# Team26vFinal.net
KiCad netlist of a schematic drawn in EAGLE
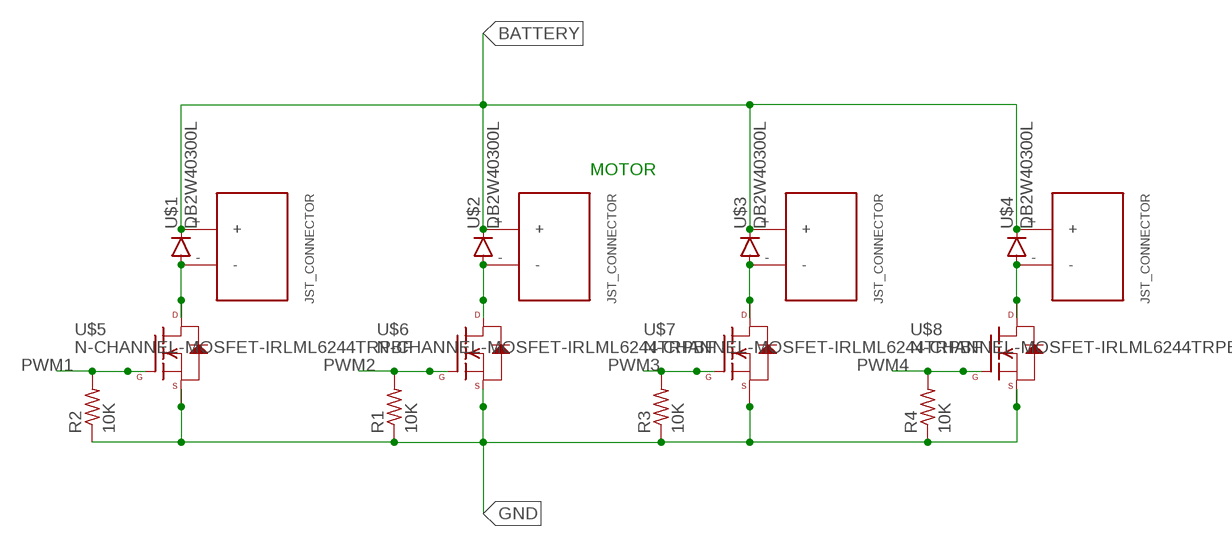
[diagram p0: schematic, sheet 1]
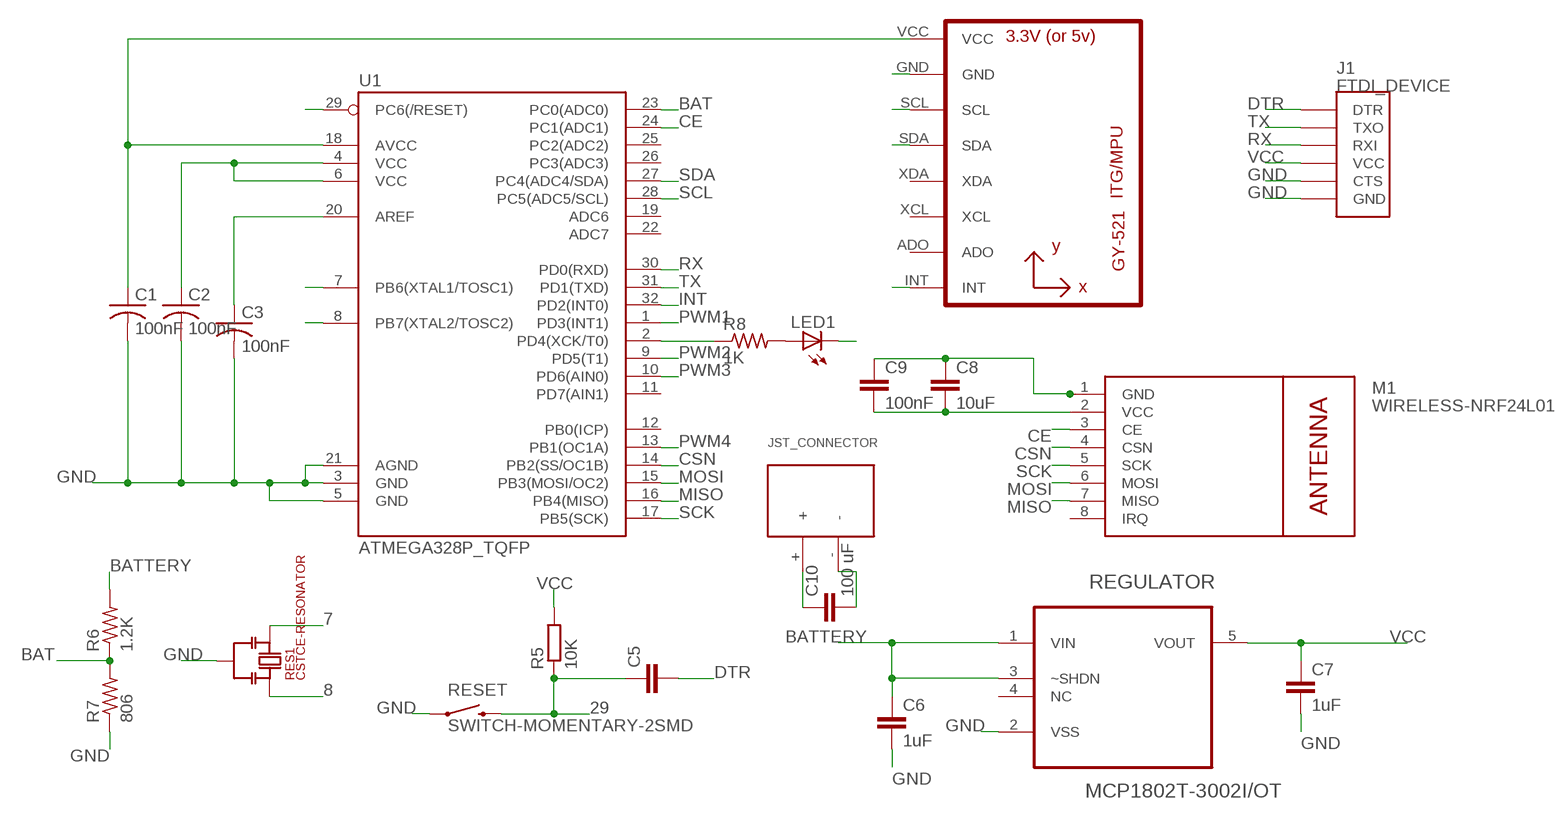
[diagram p1: schematic, sheet 2]

(export (version "E")
  (design (tool "Eeschema 10.0.6"))
  (components
    (comp (ref "C1")
      (value "100nF")
      (footprint "eagle-import:C0603")
      (libsource (lib "eagle-import") (part "C-USC0603"))
    )
    (comp (ref "C2")
      (value "100nF")
      (footprint "eagle-import:C0603")
      (libsource (lib "eagle-import") (part "C-USC0603"))
    )
    (comp (ref "C3")
      (value "100nF")
      (footprint "eagle-import:C0603")
      (libsource (lib "eagle-import") (part "C-USC0603"))
    )
    (comp (ref "C5")
      (value "C-EUC0603")
      (footprint "eagle-import:C0603")
      (libsource (lib "eagle-import") (part "C-EUC0603"))
    )
    (comp (ref "C6")
      (value "1uF")
      (footprint "eagle-import:C0603")
      (libsource (lib "eagle-import") (part "C-EUC0603"))
    )
    (comp (ref "C7")
      (value "1uF")
      (footprint "eagle-import:C0603")
      (libsource (lib "eagle-import") (part "C-EUC0603"))
    )
    (comp (ref "C8")
      (value "10uF")
      (footprint "eagle-import:C0603")
      (libsource (lib "eagle-import") (part "C-EUC0603"))
    )
    (comp (ref "C9")
      (value "100nF")
      (footprint "eagle-import:C0603")
      (libsource (lib "eagle-import") (part "C-EUC0603"))
    )
    (comp (ref "C10")
      (value "100 uF")
      (footprint "eagle-import:C1210")
      (libsource (lib "eagle-import") (part "C-EUC1210"))
    )
    (comp (ref "J1")
      (value "FTDI_DEVICE")
      (footprint "eagle-import:FTDI_DEVICE_SIDE")
      (libsource (lib "eagle-import") (part "FTDI_DEVICE"))
    )
    (comp (ref "LED1")
      (value "LEDCHIP-LED0603")
      (footprint "eagle-import:CHIP-LED0603")
      (libsource (lib "eagle-import") (part "LEDCHIP-LED0603"))
    )
    (comp (ref "M1")
      (value "WIRELESS-NRF24L01")
      (footprint "eagle-import:WIRELESS-NRF24L01")
      (libsource (lib "eagle-import") (part "WIRELESS-NRF24L01"))
    )
    (comp (ref "R5")
      (value "10K")
      (footprint "eagle-import:R0603")
      (libsource (lib "eagle-import") (part "R-EU_R0603"))
    )
    (comp (ref "R6")
      (value "1.2K")
      (footprint "eagle-import:R0603")
      (libsource (lib "eagle-import") (part "resistor_R-US_R0603"))
    )
    (comp (ref "R7")
      (value "806")
      (footprint "eagle-import:R0603")
      (libsource (lib "eagle-import") (part "resistor_R-US_R0603"))
    )
    (comp (ref "R8")
      (value "1K")
      (footprint "eagle-import:R0603")
      (libsource (lib "eagle-import") (part "resistor_R-US_R0603"))
    )
    (comp (ref "REGULATOR")
      (value "MCP1802T-3002I/OT")
      (footprint "eagle-import:SOT95P270X145-5N")
      (libsource (lib "eagle-import") (part "MCP1802T-3002I/OT"))
    )
    (comp (ref "RES1")
      (value "CSTCE-RESONATOR")
      (footprint "eagle-import:CSTCE16M0V53-R0")
      (libsource (lib "eagle-import") (part "CSTCE-RESONATOR"))
    )
    (comp (ref "RESET")
      (value "SWITCH-MOMENTARY-2SMD")
      (footprint "eagle-import:TACTILE-SWITCH-SMD")
      (libsource (lib "eagle-import") (part "SWITCH-MOMENTARY-2SMD"))
    )
    (comp (ref "U$9")
      (value "JST_CONNECTOR_FEMALE")
      (footprint "eagle-import:JST_CONNECTOR_FEMALE")
      (libsource (lib "eagle-import") (part "JST_CONNECTOR_FEMALE"))
    )
    (comp (ref "U1")
      (value "ATMEGA328P_TQFP")
      (footprint "eagle-import:TQFP32-08")
      (libsource (lib "eagle-import") (part "ATMEGA328P_TQFP"))
    )
    (comp (ref "U2")
      (value "GY-521MPU6050")
      (footprint "eagle-import:GY-521")
      (libsource (lib "eagle-import") (part "GY-521MPU6050"))
    )
    (comp (ref "MOTOR")
      (value "JST_CONNECTOR_FEMALE")
      (footprint "eagle-import:JST_CONNECTOR_FEMALE")
      (libsource (lib "eagle-import") (part "JST_CONNECTOR_FEMALE"))
    )
    (comp (ref "MOTOR1")
      (value "JST_CONNECTOR_FEMALE")
      (footprint "eagle-import:JST_CONNECTOR_FEMALE")
      (libsource (lib "eagle-import") (part "JST_CONNECTOR_FEMALE"))
    )
    (comp (ref "MOTOR2")
      (value "JST_CONNECTOR_FEMALE")
      (footprint "eagle-import:JST_CONNECTOR_FEMALE")
      (libsource (lib "eagle-import") (part "JST_CONNECTOR_FEMALE"))
    )
    (comp (ref "MOTOR3")
      (value "JST_CONNECTOR_FEMALE")
      (footprint "eagle-import:JST_CONNECTOR_FEMALE")
      (libsource (lib "eagle-import") (part "JST_CONNECTOR_FEMALE"))
    )
    (comp (ref "R1")
      (value "10K")
      (footprint "eagle-import:R0603")
      (libsource (lib "eagle-import") (part "R-US_R0603"))
    )
    (comp (ref "R2")
      (value "10K")
      (footprint "eagle-import:R0603")
      (libsource (lib "eagle-import") (part "R-US_R0603"))
    )
    (comp (ref "R3")
      (value "10K")
      (footprint "eagle-import:R0603")
      (libsource (lib "eagle-import") (part "R-US_R0603"))
    )
    (comp (ref "R4")
      (value "10K")
      (footprint "eagle-import:R0603")
      (libsource (lib "eagle-import") (part "R-US_R0603"))
    )
    (comp (ref "U$1")
      (value "DB2W40300L")
      (footprint "eagle-import:MINI2-F3-B")
      (libsource (lib "eagle-import") (part "DB2W40300L"))
    )
    (comp (ref "U$2")
      (value "DB2W40300L")
      (footprint "eagle-import:MINI2-F3-B")
      (libsource (lib "eagle-import") (part "DB2W40300L"))
    )
    (comp (ref "U$3")
      (value "DB2W40300L")
      (footprint "eagle-import:MINI2-F3-B")
      (libsource (lib "eagle-import") (part "DB2W40300L"))
    )
    (comp (ref "U$4")
      (value "DB2W40300L")
      (footprint "eagle-import:MINI2-F3-B")
      (libsource (lib "eagle-import") (part "DB2W40300L"))
    )
    (comp (ref "U$5")
      (value "N-CHANNEL-MOSFET-IRLML6244TRPBF")
      (footprint "eagle-import:SOT23-3")
      (libsource (lib "eagle-import") (part "N-CHANNEL-MOSFET-IRLML6244TRPBF"))
    )
    (comp (ref "U$6")
      (value "N-CHANNEL-MOSFET-IRLML6244TRPBF")
      (footprint "eagle-import:SOT23-3")
      (libsource (lib "eagle-import") (part "N-CHANNEL-MOSFET-IRLML6244TRPBF"))
    )
    (comp (ref "U$7")
      (value "N-CHANNEL-MOSFET-IRLML6244TRPBF")
      (footprint "eagle-import:SOT23-3")
      (libsource (lib "eagle-import") (part "N-CHANNEL-MOSFET-IRLML6244TRPBF"))
    )
    (comp (ref "U$8")
      (value "N-CHANNEL-MOSFET-IRLML6244TRPBF")
      (footprint "eagle-import:SOT23-3")
      (libsource (lib "eagle-import") (part "N-CHANNEL-MOSFET-IRLML6244TRPBF"))
    )
  )
  (nets
    (net (code "1") (name "7") (class "Default")
      (node (ref "RES1") (pin "P$3") (pinfunction "P$3_P$3") (pintype "bidirectional"))
      (node (ref "U1") (pin "7") (pinfunction "PB6(XTAL1/TOSC1)_7") (pintype "bidirectional"))
    )
    (net (code "2") (name "8") (class "Default")
      (node (ref "RES1") (pin "P$1") (pinfunction "P$1_P$1") (pintype "bidirectional"))
      (node (ref "U1") (pin "8") (pinfunction "PB7(XTAL2/TOSC2)_8") (pintype "bidirectional"))
    )
    (net (code "3") (name "29") (class "Default")
      (node (ref "C5") (pin "1") (pinfunction "1_1") (pintype "passive"))
      (node (ref "R5") (pin "1") (pinfunction "1_1") (pintype "passive"))
      (node (ref "RESET") (pin "3") (pinfunction "2_3") (pintype "passive"))
      (node (ref "U1") (pin "29") (pinfunction "PC6(/RESET)_29") (pintype "bidirectional"))
    )
    (net (code "4") (name "BAT") (class "Default")
      (node (ref "R6") (pin "1") (pinfunction "1_1") (pintype "passive"))
      (node (ref "R7") (pin "2") (pinfunction "2_2") (pintype "passive"))
      (node (ref "U1") (pin "23") (pinfunction "PC0(ADC0)_23") (pintype "bidirectional"))
    )
    (net (code "5") (name "BATTERY") (class "Default")
      (node (ref "C10") (pin "1") (pinfunction "1_1") (pintype "passive"))
      (node (ref "C6") (pin "1") (pinfunction "1_1") (pintype "passive"))
      (node (ref "MOTOR") (pin "+") (pinfunction "+_+") (pintype "bidirectional"))
      (node (ref "MOTOR1") (pin "+") (pinfunction "+_+") (pintype "bidirectional"))
      (node (ref "MOTOR2") (pin "+") (pinfunction "+_+") (pintype "bidirectional"))
      (node (ref "MOTOR3") (pin "+") (pinfunction "+_+") (pintype "bidirectional"))
      (node (ref "R6") (pin "2") (pinfunction "2_2") (pintype "passive"))
      (node (ref "REGULATOR") (pin "1") (pinfunction "VIN_1") (pintype "power_in"))
      (node (ref "REGULATOR") (pin "3") (pinfunction "~{SHDN}_3") (pintype "input"))
      (node (ref "U$1") (pin "NEG") (pinfunction "GPIN_NEG") (pintype "passive"))
      (node (ref "U$2") (pin "NEG") (pinfunction "GPIN_NEG") (pintype "passive"))
      (node (ref "U$3") (pin "NEG") (pinfunction "GPIN_NEG") (pintype "passive"))
      (node (ref "U$4") (pin "NEG") (pinfunction "GPIN_NEG") (pintype "passive"))
      (node (ref "U$9") (pin "+") (pinfunction "+_+") (pintype "bidirectional"))
    )
    (net (code "6") (name "CE") (class "Default")
      (node (ref "M1") (pin "3") (pinfunction "CE_3") (pintype "bidirectional"))
      (node (ref "U1") (pin "24") (pinfunction "PC1(ADC1)_24") (pintype "bidirectional"))
    )
    (net (code "7") (name "CSN") (class "Default")
      (node (ref "M1") (pin "4") (pinfunction "CSN_4") (pintype "bidirectional"))
      (node (ref "U1") (pin "14") (pinfunction "PB2(SS/OC1B)_14") (pintype "bidirectional"))
    )
    (net (code "8") (name "DTR") (class "Default")
      (node (ref "C5") (pin "2") (pinfunction "2_2") (pintype "passive"))
      (node (ref "J1") (pin "P$1") (pinfunction "DTR_P$1") (pintype "bidirectional"))
    )
    (net (code "9") (name "GND") (class "Default")
      (node (ref "C1") (pin "2") (pinfunction "2_2") (pintype "passive"))
      (node (ref "C10") (pin "2") (pinfunction "2_2") (pintype "passive"))
      (node (ref "C2") (pin "2") (pinfunction "2_2") (pintype "passive"))
      (node (ref "C3") (pin "2") (pinfunction "2_2") (pintype "passive"))
      (node (ref "C6") (pin "2") (pinfunction "2_2") (pintype "passive"))
      (node (ref "C7") (pin "2") (pinfunction "2_2") (pintype "passive"))
      (node (ref "C8") (pin "1") (pinfunction "1_1") (pintype "passive"))
      (node (ref "C9") (pin "1") (pinfunction "1_1") (pintype "passive"))
      (node (ref "J1") (pin "P$5") (pinfunction "CTS_P$5") (pintype "bidirectional"))
      (node (ref "J1") (pin "P$6") (pinfunction "GND_P$6") (pintype "bidirectional"))
      (node (ref "LED1") (pin "C") (pinfunction "C_C") (pintype "passive"))
      (node (ref "M1") (pin "1") (pinfunction "GND_1") (pintype "power_in"))
      (node (ref "R1") (pin "1") (pinfunction "1_1") (pintype "passive"))
      (node (ref "R2") (pin "1") (pinfunction "1_1") (pintype "passive"))
      (node (ref "R3") (pin "1") (pinfunction "1_1") (pintype "passive"))
      (node (ref "R4") (pin "1") (pinfunction "1_1") (pintype "passive"))
      (node (ref "R7") (pin "1") (pinfunction "1_1") (pintype "passive"))
      (node (ref "REGULATOR") (pin "2") (pinfunction "VSS_2") (pintype "passive"))
      (node (ref "RES1") (pin "P$2") (pinfunction "P$2_P$2") (pintype "bidirectional"))
      (node (ref "RESET") (pin "1") (pinfunction "1_1") (pintype "passive"))
      (node (ref "U$5") (pin "2") (pinfunction "S_2") (pintype "passive"))
      (node (ref "U$6") (pin "2") (pinfunction "S_2") (pintype "passive"))
      (node (ref "U$7") (pin "2") (pinfunction "S_2") (pintype "passive"))
      (node (ref "U$8") (pin "2") (pinfunction "S_2") (pintype "passive"))
      (node (ref "U$9") (pin "-") (pinfunction "-_-") (pintype "bidirectional"))
      (node (ref "U1") (pin "21") (pinfunction "AGND_21") (pintype "bidirectional"))
      (node (ref "U1") (pin "3") (pinfunction "GND_3") (pintype "bidirectional"))
      (node (ref "U1") (pin "5") (pinfunction "GND_5") (pintype "bidirectional"))
      (node (ref "U2") (pin "GND") (pinfunction "GND_GND") (pintype "bidirectional"))
    )
    (net (code "10") (name "INT") (class "Default")
      (node (ref "U1") (pin "32") (pinfunction "PD2(INT0)_32") (pintype "bidirectional"))
      (node (ref "U2") (pin "INT") (pinfunction "INT_INT") (pintype "bidirectional"))
    )
    (net (code "11") (name "MISO") (class "Default")
      (node (ref "M1") (pin "7") (pinfunction "MISO_7") (pintype "bidirectional"))
      (node (ref "U1") (pin "16") (pinfunction "PB4(MISO)_16") (pintype "bidirectional"))
    )
    (net (code "12") (name "MOSI") (class "Default")
      (node (ref "M1") (pin "6") (pinfunction "MOSI_6") (pintype "bidirectional"))
      (node (ref "U1") (pin "15") (pinfunction "PB3(MOSI/OC2)_15") (pintype "bidirectional"))
    )
    (net (code "13") (name "Net-(LED1-PadA)") (class "Default")
      (node (ref "LED1") (pin "A") (pinfunction "A_A") (pintype "passive"))
      (node (ref "R8") (pin "2") (pinfunction "2_2") (pintype "passive"))
    )
    (net (code "14") (name "Net-(U$1-PPIN)") (class "Default")
      (node (ref "MOTOR1") (pin "-") (pinfunction "-_-") (pintype "bidirectional"))
      (node (ref "U$1") (pin "POS") (pinfunction "PPIN_POS") (pintype "passive"))
      (node (ref "U$5") (pin "3") (pinfunction "D_3") (pintype "passive"))
    )
    (net (code "15") (name "Net-(U$2-PPIN)") (class "Default")
      (node (ref "MOTOR") (pin "-") (pinfunction "-_-") (pintype "bidirectional"))
      (node (ref "U$2") (pin "POS") (pinfunction "PPIN_POS") (pintype "passive"))
      (node (ref "U$6") (pin "3") (pinfunction "D_3") (pintype "passive"))
    )
    (net (code "16") (name "Net-(U$3-PPIN)") (class "Default")
      (node (ref "MOTOR2") (pin "-") (pinfunction "-_-") (pintype "bidirectional"))
      (node (ref "U$3") (pin "POS") (pinfunction "PPIN_POS") (pintype "passive"))
      (node (ref "U$7") (pin "3") (pinfunction "D_3") (pintype "passive"))
    )
    (net (code "17") (name "Net-(U$4-PPIN)") (class "Default")
      (node (ref "MOTOR3") (pin "-") (pinfunction "-_-") (pintype "bidirectional"))
      (node (ref "U$4") (pin "POS") (pinfunction "PPIN_POS") (pintype "passive"))
      (node (ref "U$8") (pin "3") (pinfunction "D_3") (pintype "passive"))
    )
    (net (code "18") (name "Net-(U1-AREF)") (class "Default")
      (node (ref "C3") (pin "1") (pinfunction "1_1") (pintype "passive"))
      (node (ref "U1") (pin "20") (pinfunction "AREF_20") (pintype "bidirectional"))
    )
    (net (code "19") (name "Net-(U1-PD4(XCK{slash}T0))") (class "Default")
      (node (ref "R8") (pin "1") (pinfunction "1_1") (pintype "passive"))
      (node (ref "U1") (pin "2") (pinfunction "PD4(XCK/T0)_2") (pintype "bidirectional"))
    )
    (net (code "20") (name "PWM1") (class "Default")
      (node (ref "R2") (pin "2") (pinfunction "2_2") (pintype "passive"))
      (node (ref "U$5") (pin "1") (pinfunction "G_1") (pintype "passive"))
      (node (ref "U1") (pin "1") (pinfunction "PD3(INT1)_1") (pintype "bidirectional"))
    )
    (net (code "21") (name "PWM2") (class "Default")
      (node (ref "R1") (pin "2") (pinfunction "2_2") (pintype "passive"))
      (node (ref "U$6") (pin "1") (pinfunction "G_1") (pintype "passive"))
      (node (ref "U1") (pin "9") (pinfunction "PD5(T1)_9") (pintype "bidirectional"))
    )
    (net (code "22") (name "PWM3") (class "Default")
      (node (ref "R3") (pin "2") (pinfunction "2_2") (pintype "passive"))
      (node (ref "U$7") (pin "1") (pinfunction "G_1") (pintype "passive"))
      (node (ref "U1") (pin "10") (pinfunction "PD6(AIN0)_10") (pintype "bidirectional"))
    )
    (net (code "23") (name "PWM4") (class "Default")
      (node (ref "R4") (pin "2") (pinfunction "2_2") (pintype "passive"))
      (node (ref "U$8") (pin "1") (pinfunction "G_1") (pintype "passive"))
      (node (ref "U1") (pin "13") (pinfunction "PB1(OC1A)_13") (pintype "bidirectional"))
    )
    (net (code "24") (name "RX") (class "Default")
      (node (ref "J1") (pin "P$3") (pinfunction "RXI_P$3") (pintype "bidirectional"))
      (node (ref "U1") (pin "30") (pinfunction "PD0(RXD)_30") (pintype "bidirectional"))
    )
    (net (code "25") (name "SCK") (class "Default")
      (node (ref "M1") (pin "5") (pinfunction "SCK_5") (pintype "bidirectional"))
      (node (ref "U1") (pin "17") (pinfunction "PB5(SCK)_17") (pintype "bidirectional"))
    )
    (net (code "26") (name "SCL") (class "Default")
      (node (ref "U1") (pin "28") (pinfunction "PC5(ADC5/SCL)_28") (pintype "bidirectional"))
      (node (ref "U2") (pin "SCL") (pinfunction "SCL_SCL") (pintype "bidirectional"))
    )
    (net (code "27") (name "SDA") (class "Default")
      (node (ref "U1") (pin "27") (pinfunction "PC4(ADC4/SDA)_27") (pintype "bidirectional"))
      (node (ref "U2") (pin "SDA") (pinfunction "SDA_SDA") (pintype "bidirectional"))
    )
    (net (code "28") (name "TX") (class "Default")
      (node (ref "J1") (pin "P$2") (pinfunction "TXO_P$2") (pintype "bidirectional"))
      (node (ref "U1") (pin "31") (pinfunction "PD1(TXD)_31") (pintype "bidirectional"))
    )
    (net (code "29") (name "VCC") (class "Default")
      (node (ref "C1") (pin "1") (pinfunction "1_1") (pintype "passive"))
      (node (ref "C2") (pin "1") (pinfunction "1_1") (pintype "passive"))
      (node (ref "C7") (pin "1") (pinfunction "1_1") (pintype "passive"))
      (node (ref "C8") (pin "2") (pinfunction "2_2") (pintype "passive"))
      (node (ref "C9") (pin "2") (pinfunction "2_2") (pintype "passive"))
      (node (ref "J1") (pin "P$4") (pinfunction "VCC_P$4") (pintype "bidirectional"))
      (node (ref "M1") (pin "2") (pinfunction "VCC_2") (pintype "power_in"))
      (node (ref "R5") (pin "2") (pinfunction "2_2") (pintype "passive"))
      (node (ref "REGULATOR") (pin "5") (pinfunction "VOUT_5") (pintype "output"))
      (node (ref "U1") (pin "18") (pinfunction "AVCC_18") (pintype "bidirectional"))
      (node (ref "U1") (pin "4") (pinfunction "VCC_4") (pintype "bidirectional"))
      (node (ref "U1") (pin "6") (pinfunction "VCC_6") (pintype "bidirectional"))
      (node (ref "U2") (pin "VCC") (pinfunction "VCC_VCC") (pintype "bidirectional"))
    )
    (net (code "30") (name "unconnected-(M1-IRQ-Pad8)") (class "Default")
      (node (ref "M1") (pin "8") (pinfunction "IRQ_8") (pintype "bidirectional"))
    )
    (net (code "31") (name "unconnected-(REGULATOR-NC-Pad4)") (class "Default")
      (node (ref "REGULATOR") (pin "4") (pinfunction "NC_4") (pintype "no_connect"))
    )
    (net (code "32") (name "unconnected-(U1-ADC6-Pad19)") (class "Default")
      (node (ref "U1") (pin "19") (pinfunction "ADC6_19") (pintype "bidirectional"))
    )
    (net (code "33") (name "unconnected-(U1-ADC7-Pad22)") (class "Default")
      (node (ref "U1") (pin "22") (pinfunction "ADC7_22") (pintype "bidirectional"))
    )
    (net (code "34") (name "unconnected-(U1-PB0(ICP)-Pad12)") (class "Default")
      (node (ref "U1") (pin "12") (pinfunction "PB0(ICP)_12") (pintype "bidirectional"))
    )
    (net (code "35") (name "unconnected-(U1-PC2(ADC2)-Pad25)") (class "Default")
      (node (ref "U1") (pin "25") (pinfunction "PC2(ADC2)_25") (pintype "bidirectional"))
    )
    (net (code "36") (name "unconnected-(U1-PC3(ADC3)-Pad26)") (class "Default")
      (node (ref "U1") (pin "26") (pinfunction "PC3(ADC3)_26") (pintype "bidirectional"))
    )
    (net (code "37") (name "unconnected-(U1-PD7(AIN1)-Pad11)") (class "Default")
      (node (ref "U1") (pin "11") (pinfunction "PD7(AIN1)_11") (pintype "bidirectional"))
    )
    (net (code "38") (name "unconnected-(U2-PadADO)") (class "Default")
      (node (ref "U2") (pin "ADO") (pinfunction "ADO_ADO") (pintype "bidirectional"))
    )
    (net (code "39") (name "unconnected-(U2-PadXCL)") (class "Default")
      (node (ref "U2") (pin "XCL") (pinfunction "XCL_XCL") (pintype "bidirectional"))
    )
    (net (code "40") (name "unconnected-(U2-PadXDA)") (class "Default")
      (node (ref "U2") (pin "XDA") (pinfunction "XDA_XDA") (pintype "bidirectional"))
    )
  )
)
